# SCH__17Toutch__2024-07-19.net
KiCad netlist of a schematic drawn in EasyEDA
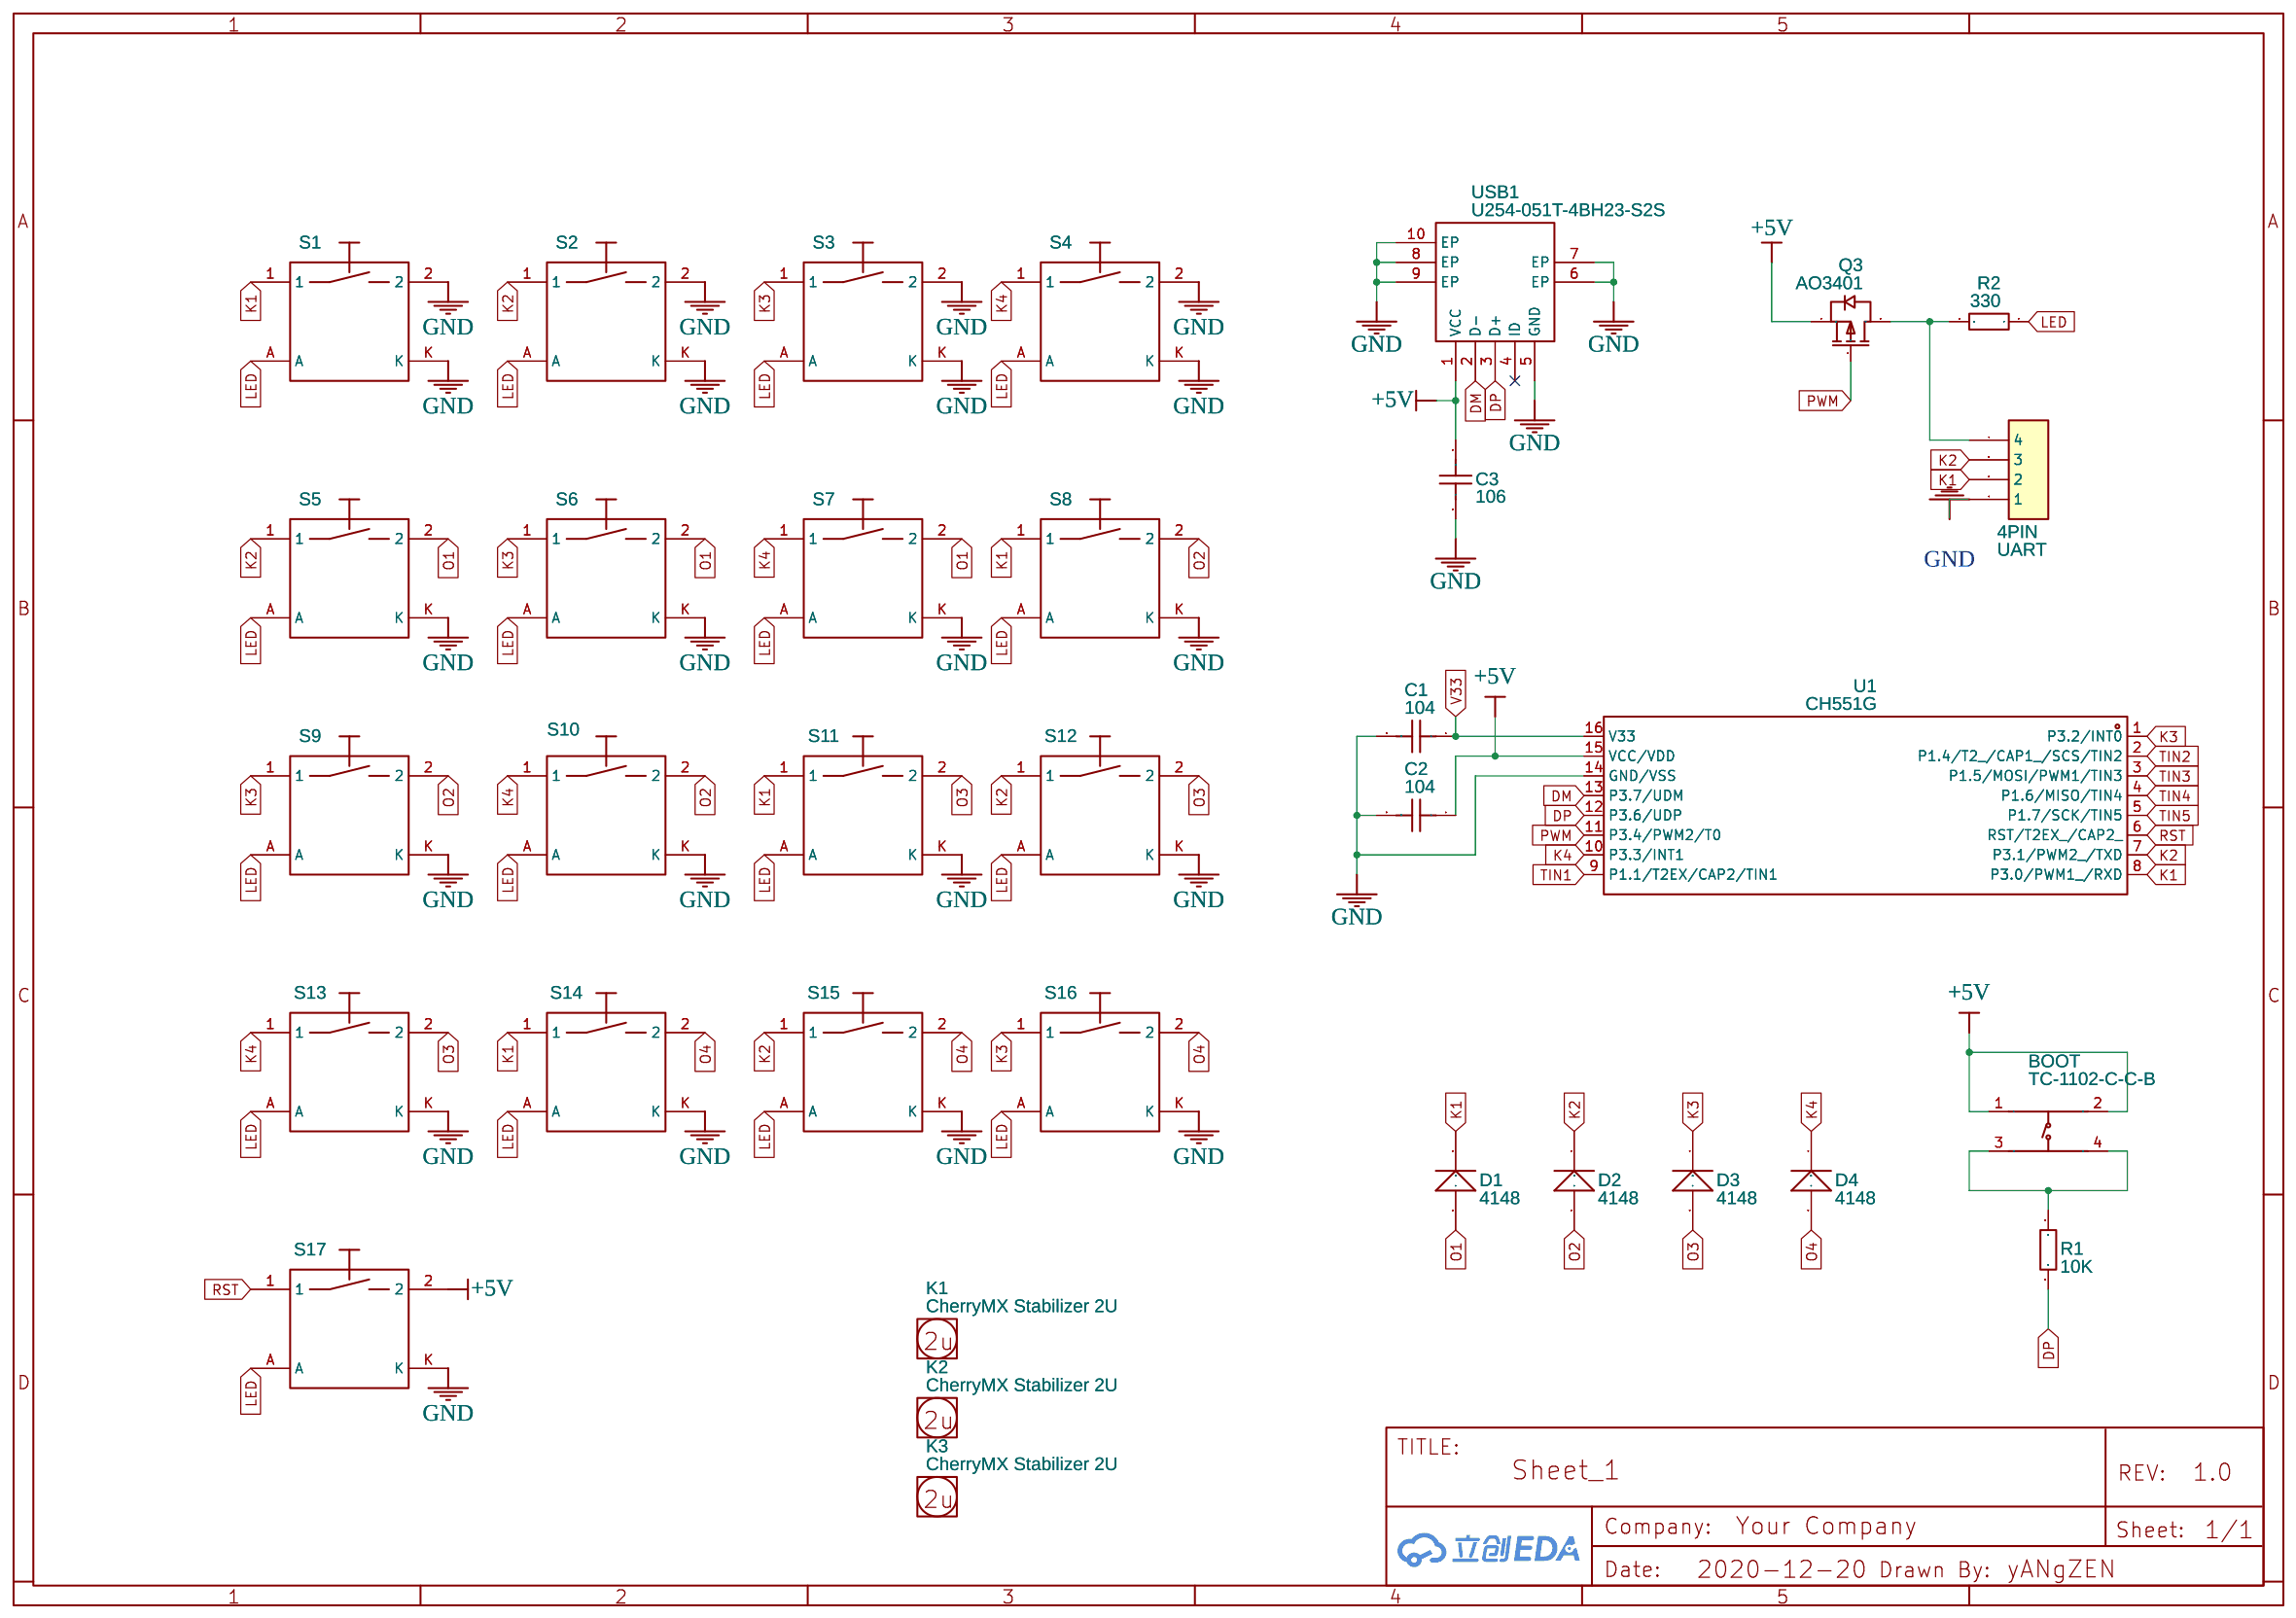
[diagram p0: schematic sheet]

(export (version "E")
  (design (tool "Eeschema 10.0.6"))
  (components
    (comp (ref "BOOT")
      (value "TC-1102-C-C-B")
      (fields (field (name "Manufacturer") "XKB Enterprise"))
      (libsource (lib "") (part "TS665CJ"))
    )
    (comp (ref "C1")
      (value "104")
      (fields
        (field (name "Manufacturer Part") "0603B331K251CT")
        (field (name "Manufacturer") "Walsin Tech Corp")
      )
      (libsource (lib "") (part "0603B331K251CT"))
    )
    (comp (ref "C2")
      (value "104")
      (fields
        (field (name "Manufacturer Part") "0603B331K251CT")
        (field (name "Manufacturer") "Walsin Tech Corp")
      )
      (libsource (lib "") (part "0603B331K251CT"))
    )
    (comp (ref "C3")
      (value "106")
      (fields
        (field (name "Manufacturer Part") "0603B331K251CT")
        (field (name "Manufacturer") "Walsin Tech Corp")
      )
      (libsource (lib "") (part "0603B331K251CT_1"))
    )
    (comp (ref "D1")
      (value "4148")
      (fields (field (name "Manufacturer Part") "TCLL4148") (field (name "Manufacturer") "Tak Cheong"))
      (libsource (lib "") (part "TCLL4148"))
    )
    (comp (ref "D2")
      (value "4148")
      (fields (field (name "Manufacturer Part") "TCLL4148") (field (name "Manufacturer") "Tak Cheong"))
      (libsource (lib "") (part "TCLL4148"))
    )
    (comp (ref "D3")
      (value "4148")
      (fields (field (name "Manufacturer Part") "TCLL4148") (field (name "Manufacturer") "Tak Cheong"))
      (libsource (lib "") (part "TCLL4148"))
    )
    (comp (ref "D4")
      (value "4148")
      (fields (field (name "Manufacturer Part") "TCLL4148") (field (name "Manufacturer") "Tak Cheong"))
      (libsource (lib "") (part "TCLL4148"))
    )
    (comp (ref "K1")
      (value "CherryMX Stabilizer 2U")
      (fields (field (name "Manufacturer Part") "Cherry MX"))
      (libsource (lib "") (part "CherryMX Stabilizer 2U"))
    )
    (comp (ref "K2")
      (value "CherryMX Stabilizer 2U")
      (fields (field (name "Manufacturer Part") "Cherry MX"))
      (libsource (lib "") (part "CherryMX Stabilizer 2U"))
    )
    (comp (ref "K3")
      (value "CherryMX Stabilizer 2U")
      (fields (field (name "Manufacturer Part") "Cherry MX"))
      (libsource (lib "") (part "CherryMX Stabilizer 2U"))
    )
    (comp (ref "Q3")
      (value "AO3401")
      (fields (field (name "Manufacturer") "Foshan Blue Rocket Elec"))
      (libsource (lib "") (part "AO3401_C305433"))
    )
    (comp (ref "R1")
      (value "10K")
      (fields (field (name "Manufacturer Part") "AC0603FR-07210KL") (field (name "Manufacturer") "YAGEO"))
      (libsource (lib "") (part "AC0603FR-07210KL"))
    )
    (comp (ref "R2")
      (value "330")
      (fields (field (name "Manufacturer Part") "AC0603FR-07210KL") (field (name "Manufacturer") "YAGEO"))
      (libsource (lib "") (part "AC0603FR-07210KL_1"))
    )
    (comp (ref "S1") (value "高特插拔轴（两脚F3）") (libsource (lib "") (part "高特插拔轴（两脚F3）")))
    (comp (ref "S2") (value "高特插拔轴（两脚F3）") (libsource (lib "") (part "高特插拔轴（两脚F3）")))
    (comp (ref "S3") (value "高特插拔轴（两脚F3）") (libsource (lib "") (part "高特插拔轴（两脚F3）")))
    (comp (ref "S4") (value "高特插拔轴（两脚F3）") (libsource (lib "") (part "高特插拔轴（两脚F3）")))
    (comp (ref "S5") (value "高特插拔轴（两脚F3）") (libsource (lib "") (part "高特插拔轴（两脚F3）")))
    (comp (ref "S6") (value "高特插拔轴（两脚F3）") (libsource (lib "") (part "高特插拔轴（两脚F3）")))
    (comp (ref "S7") (value "高特插拔轴（两脚F3）") (libsource (lib "") (part "高特插拔轴（两脚F3）")))
    (comp (ref "S8") (value "高特插拔轴（两脚F3）") (libsource (lib "") (part "高特插拔轴（两脚F3）")))
    (comp (ref "S9") (value "高特插拔轴（两脚F3）") (libsource (lib "") (part "高特插拔轴（两脚F3）")))
    (comp (ref "S10") (value "高特插拔轴（两脚F3）") (libsource (lib "") (part "高特插拔轴（两脚F3）")))
    (comp (ref "S11") (value "高特插拔轴（两脚F3）") (libsource (lib "") (part "高特插拔轴（两脚F3）")))
    (comp (ref "S12") (value "高特插拔轴（两脚F3）") (libsource (lib "") (part "高特插拔轴（两脚F3）")))
    (comp (ref "S13") (value "高特插拔轴（两脚F3）") (libsource (lib "") (part "高特插拔轴（两脚F3）")))
    (comp (ref "S14") (value "高特插拔轴（两脚F3）") (libsource (lib "") (part "高特插拔轴（两脚F3）")))
    (comp (ref "S15") (value "高特插拔轴（两脚F3）") (libsource (lib "") (part "高特插拔轴（两脚F3）")))
    (comp (ref "S16") (value "高特插拔轴（两脚F3）") (libsource (lib "") (part "高特插拔轴（两脚F3）")))
    (comp (ref "S17") (value "高特插拔轴（两脚F3）") (libsource (lib "") (part "高特插拔轴（两脚F3）")))
    (comp (ref "U1")
      (value "CH551G")
      (fields (field (name "Manufacturer") "WCH"))
      (libsource (lib "") (part "CH551G"))
    )
    (comp (ref "UART")
      (value "4PIN")
      (fields
        (field (name "Manufacturer Part") "X6511WV-04H-C30D60")
        (field (name "Manufacturer") "XKB Connectivity")
      )
      (libsource (lib "") (part "4PIN"))
    )
    (comp (ref "USB1")
      (value "U254-051T-4BH23-S2S")
      (fields (field (name "Manufacturer") "XKB Enterprise"))
      (libsource (lib "") (part "105017-0001"))
    )
  )
  (nets
    (net (code "1") (name "+5V") (class "Default")
      (node (ref "BOOT") (pin "1") (pinfunction "A_1") (pintype "unspecified"))
      (node (ref "BOOT") (pin "2") (pinfunction "B_2") (pintype "unspecified"))
      (node (ref "C2") (pin "1") (pinfunction "1_1") (pintype "unspecified"))
      (node (ref "C3") (pin "1") (pinfunction "1_1") (pintype "unspecified"))
      (node (ref "Q3") (pin "2") (pinfunction "S_2") (pintype "unspecified"))
      (node (ref "S17") (pin "2") (pinfunction "2_2") (pintype "unspecified"))
      (node (ref "U1") (pin "15") (pinfunction "VCC/VDD_15") (pintype "unspecified"))
      (node (ref "USB1") (pin "1") (pinfunction "VCC_1") (pintype "unspecified"))
    )
    (net (code "2") (name "DM") (class "Default")
      (node (ref "U1") (pin "13") (pinfunction "P3.7/UDM_13") (pintype "unspecified"))
      (node (ref "USB1") (pin "2") (pinfunction "D-_2") (pintype "unspecified"))
    )
    (net (code "3") (name "DP") (class "Default")
      (node (ref "R1") (pin "2") (pinfunction "2_2") (pintype "unspecified"))
      (node (ref "U1") (pin "12") (pinfunction "P3.6/UDP_12") (pintype "unspecified"))
      (node (ref "USB1") (pin "3") (pinfunction "D+_3") (pintype "unspecified"))
    )
    (net (code "4") (name "GND") (class "Default")
      (node (ref "C1") (pin "2") (pinfunction "2_2") (pintype "unspecified"))
      (node (ref "C2") (pin "2") (pinfunction "2_2") (pintype "unspecified"))
      (node (ref "C3") (pin "2") (pinfunction "2_2") (pintype "unspecified"))
      (node (ref "S1") (pin "2") (pinfunction "2_2") (pintype "unspecified"))
      (node (ref "S1") (pin "K") (pinfunction "K_K") (pintype "unspecified"))
      (node (ref "S10") (pin "K") (pinfunction "K_K") (pintype "unspecified"))
      (node (ref "S11") (pin "K") (pinfunction "K_K") (pintype "unspecified"))
      (node (ref "S12") (pin "K") (pinfunction "K_K") (pintype "unspecified"))
      (node (ref "S13") (pin "K") (pinfunction "K_K") (pintype "unspecified"))
      (node (ref "S14") (pin "K") (pinfunction "K_K") (pintype "unspecified"))
      (node (ref "S15") (pin "K") (pinfunction "K_K") (pintype "unspecified"))
      (node (ref "S16") (pin "K") (pinfunction "K_K") (pintype "unspecified"))
      (node (ref "S17") (pin "K") (pinfunction "K_K") (pintype "unspecified"))
      (node (ref "S2") (pin "2") (pinfunction "2_2") (pintype "unspecified"))
      (node (ref "S2") (pin "K") (pinfunction "K_K") (pintype "unspecified"))
      (node (ref "S3") (pin "2") (pinfunction "2_2") (pintype "unspecified"))
      (node (ref "S3") (pin "K") (pinfunction "K_K") (pintype "unspecified"))
      (node (ref "S4") (pin "2") (pinfunction "2_2") (pintype "unspecified"))
      (node (ref "S4") (pin "K") (pinfunction "K_K") (pintype "unspecified"))
      (node (ref "S5") (pin "K") (pinfunction "K_K") (pintype "unspecified"))
      (node (ref "S6") (pin "K") (pinfunction "K_K") (pintype "unspecified"))
      (node (ref "S7") (pin "K") (pinfunction "K_K") (pintype "unspecified"))
      (node (ref "S8") (pin "K") (pinfunction "K_K") (pintype "unspecified"))
      (node (ref "S9") (pin "K") (pinfunction "K_K") (pintype "unspecified"))
      (node (ref "U1") (pin "14") (pinfunction "GND/VSS_14") (pintype "unspecified"))
      (node (ref "UART") (pin "1") (pinfunction "1_1") (pintype "unspecified"))
      (node (ref "USB1") (pin "10") (pinfunction "EP_10") (pintype "unspecified"))
      (node (ref "USB1") (pin "5") (pinfunction "GND_5") (pintype "unspecified"))
      (node (ref "USB1") (pin "6") (pinfunction "EP_6") (pintype "unspecified"))
      (node (ref "USB1") (pin "7") (pinfunction "EP_7") (pintype "unspecified"))
      (node (ref "USB1") (pin "8") (pinfunction "EP_8") (pintype "unspecified"))
      (node (ref "USB1") (pin "9") (pinfunction "EP_9") (pintype "unspecified"))
    )
    (net (code "5") (name "K1") (class "Default")
      (node (ref "D1") (pin "1") (pinfunction "C_1") (pintype "unspecified"))
      (node (ref "S1") (pin "1") (pinfunction "1_1") (pintype "unspecified"))
      (node (ref "S11") (pin "1") (pinfunction "1_1") (pintype "unspecified"))
      (node (ref "S14") (pin "1") (pinfunction "1_1") (pintype "unspecified"))
      (node (ref "S8") (pin "1") (pinfunction "1_1") (pintype "unspecified"))
      (node (ref "U1") (pin "8") (pinfunction "P3.0/PWM1_/RXD_8") (pintype "unspecified"))
      (node (ref "UART") (pin "2") (pinfunction "2_2") (pintype "unspecified"))
    )
    (net (code "6") (name "K2") (class "Default")
      (node (ref "D2") (pin "1") (pinfunction "C_1") (pintype "unspecified"))
      (node (ref "S12") (pin "1") (pinfunction "1_1") (pintype "unspecified"))
      (node (ref "S15") (pin "1") (pinfunction "1_1") (pintype "unspecified"))
      (node (ref "S2") (pin "1") (pinfunction "1_1") (pintype "unspecified"))
      (node (ref "S5") (pin "1") (pinfunction "1_1") (pintype "unspecified"))
      (node (ref "U1") (pin "7") (pinfunction "P3.1/PWM2_/TXD_7") (pintype "unspecified"))
      (node (ref "UART") (pin "3") (pinfunction "3_3") (pintype "unspecified"))
    )
    (net (code "7") (name "K3") (class "Default")
      (node (ref "D3") (pin "1") (pinfunction "C_1") (pintype "unspecified"))
      (node (ref "S16") (pin "1") (pinfunction "1_1") (pintype "unspecified"))
      (node (ref "S3") (pin "1") (pinfunction "1_1") (pintype "unspecified"))
      (node (ref "S6") (pin "1") (pinfunction "1_1") (pintype "unspecified"))
      (node (ref "S9") (pin "1") (pinfunction "1_1") (pintype "unspecified"))
      (node (ref "U1") (pin "1") (pinfunction "P3.2/INT0_1") (pintype "unspecified"))
    )
    (net (code "8") (name "K4") (class "Default")
      (node (ref "D4") (pin "1") (pinfunction "C_1") (pintype "unspecified"))
      (node (ref "S10") (pin "1") (pinfunction "1_1") (pintype "unspecified"))
      (node (ref "S13") (pin "1") (pinfunction "1_1") (pintype "unspecified"))
      (node (ref "S4") (pin "1") (pinfunction "1_1") (pintype "unspecified"))
      (node (ref "S7") (pin "1") (pinfunction "1_1") (pintype "unspecified"))
      (node (ref "U1") (pin "10") (pinfunction "P3.3/INT1_10") (pintype "unspecified"))
    )
    (net (code "9") (name "LED") (class "Default")
      (node (ref "R2") (pin "1") (pinfunction "1_1") (pintype "unspecified"))
      (node (ref "S1") (pin "A") (pinfunction "A_A") (pintype "unspecified"))
      (node (ref "S10") (pin "A") (pinfunction "A_A") (pintype "unspecified"))
      (node (ref "S11") (pin "A") (pinfunction "A_A") (pintype "unspecified"))
      (node (ref "S12") (pin "A") (pinfunction "A_A") (pintype "unspecified"))
      (node (ref "S13") (pin "A") (pinfunction "A_A") (pintype "unspecified"))
      (node (ref "S14") (pin "A") (pinfunction "A_A") (pintype "unspecified"))
      (node (ref "S15") (pin "A") (pinfunction "A_A") (pintype "unspecified"))
      (node (ref "S16") (pin "A") (pinfunction "A_A") (pintype "unspecified"))
      (node (ref "S17") (pin "A") (pinfunction "A_A") (pintype "unspecified"))
      (node (ref "S2") (pin "A") (pinfunction "A_A") (pintype "unspecified"))
      (node (ref "S3") (pin "A") (pinfunction "A_A") (pintype "unspecified"))
      (node (ref "S4") (pin "A") (pinfunction "A_A") (pintype "unspecified"))
      (node (ref "S5") (pin "A") (pinfunction "A_A") (pintype "unspecified"))
      (node (ref "S6") (pin "A") (pinfunction "A_A") (pintype "unspecified"))
      (node (ref "S7") (pin "A") (pinfunction "A_A") (pintype "unspecified"))
      (node (ref "S8") (pin "A") (pinfunction "A_A") (pintype "unspecified"))
      (node (ref "S9") (pin "A") (pinfunction "A_A") (pintype "unspecified"))
    )
    (net (code "10") (name "Net-(BOOT-C)") (class "Default")
      (node (ref "BOOT") (pin "3") (pinfunction "C_3") (pintype "unspecified"))
      (node (ref "BOOT") (pin "4") (pinfunction "D_4") (pintype "unspecified"))
      (node (ref "R1") (pin "1") (pinfunction "1_1") (pintype "unspecified"))
    )
    (net (code "11") (name "Net-(Q3-D)") (class "Default")
      (node (ref "Q3") (pin "3") (pinfunction "D_3") (pintype "unspecified"))
      (node (ref "R2") (pin "2") (pinfunction "2_2") (pintype "unspecified"))
      (node (ref "UART") (pin "4") (pinfunction "4_4") (pintype "unspecified"))
    )
    (net (code "12") (name "O1") (class "Default")
      (node (ref "D1") (pin "2") (pinfunction "A_2") (pintype "unspecified"))
      (node (ref "S5") (pin "2") (pinfunction "2_2") (pintype "unspecified"))
      (node (ref "S6") (pin "2") (pinfunction "2_2") (pintype "unspecified"))
      (node (ref "S7") (pin "2") (pinfunction "2_2") (pintype "unspecified"))
    )
    (net (code "13") (name "O2") (class "Default")
      (node (ref "D2") (pin "2") (pinfunction "A_2") (pintype "unspecified"))
      (node (ref "S10") (pin "2") (pinfunction "2_2") (pintype "unspecified"))
      (node (ref "S8") (pin "2") (pinfunction "2_2") (pintype "unspecified"))
      (node (ref "S9") (pin "2") (pinfunction "2_2") (pintype "unspecified"))
    )
    (net (code "14") (name "O3") (class "Default")
      (node (ref "D3") (pin "2") (pinfunction "A_2") (pintype "unspecified"))
      (node (ref "S11") (pin "2") (pinfunction "2_2") (pintype "unspecified"))
      (node (ref "S12") (pin "2") (pinfunction "2_2") (pintype "unspecified"))
      (node (ref "S13") (pin "2") (pinfunction "2_2") (pintype "unspecified"))
    )
    (net (code "15") (name "O4") (class "Default")
      (node (ref "D4") (pin "2") (pinfunction "A_2") (pintype "unspecified"))
      (node (ref "S14") (pin "2") (pinfunction "2_2") (pintype "unspecified"))
      (node (ref "S15") (pin "2") (pinfunction "2_2") (pintype "unspecified"))
      (node (ref "S16") (pin "2") (pinfunction "2_2") (pintype "unspecified"))
    )
    (net (code "16") (name "PWM") (class "Default")
      (node (ref "Q3") (pin "1") (pinfunction "G_1") (pintype "unspecified"))
      (node (ref "U1") (pin "11") (pinfunction "P3.4/PWM2/T0_11") (pintype "unspecified"))
    )
    (net (code "17") (name "RST") (class "Default")
      (node (ref "S17") (pin "1") (pinfunction "1_1") (pintype "unspecified"))
      (node (ref "U1") (pin "6") (pinfunction "RST/T2EX_/CAP2__6") (pintype "unspecified"))
    )
    (net (code "18") (name "TIN1") (class "Default")
      (node (ref "U1") (pin "9") (pinfunction "P1.1/T2EX/CAP2/TIN1_9") (pintype "unspecified"))
    )
    (net (code "19") (name "TIN2") (class "Default")
      (node (ref "U1") (pin "2") (pinfunction "P1.4/T2_/CAP1_/SCS/TIN2_2") (pintype "unspecified"))
    )
    (net (code "20") (name "TIN3") (class "Default")
      (node (ref "U1") (pin "3") (pinfunction "P1.5/MOSI/PWM1/TIN3_3") (pintype "unspecified"))
    )
    (net (code "21") (name "TIN4") (class "Default")
      (node (ref "U1") (pin "4") (pinfunction "P1.6/MISO/TIN4_4") (pintype "unspecified"))
    )
    (net (code "22") (name "TIN5") (class "Default")
      (node (ref "U1") (pin "5") (pinfunction "P1.7/SCK/TIN5_5") (pintype "unspecified"))
    )
    (net (code "23") (name "V33") (class "Default")
      (node (ref "C1") (pin "1") (pinfunction "1_1") (pintype "unspecified"))
      (node (ref "U1") (pin "16") (pinfunction "V33_16") (pintype "unspecified"))
    )
    (net (code "24") (name "unconnected-(USB1-ID-Pad4)") (class "Default")
      (node (ref "USB1") (pin "4") (pinfunction "ID_4") (pintype "unspecified+no_connect"))
    )
  )
)
